# MLX.net
KiCad netlist of a schematic drawn in Altium Designer
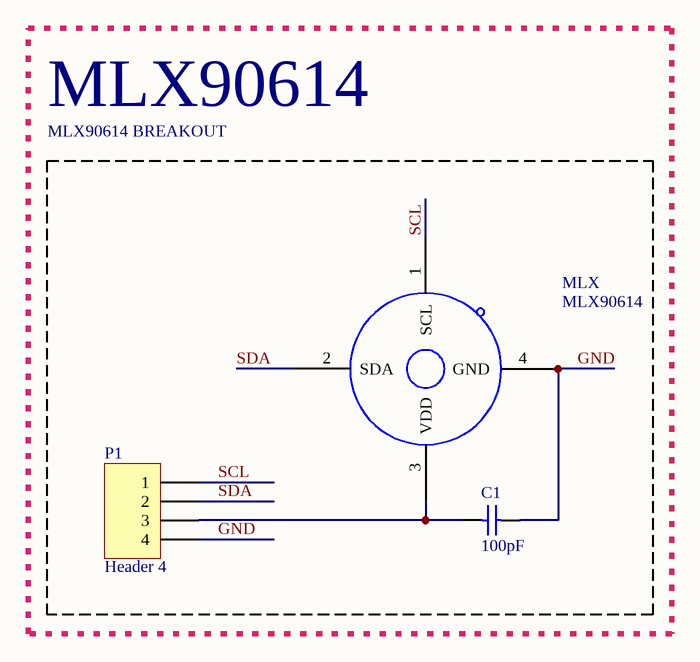
[diagram p0: MLX.SchDoc]

(export (version "E")
  (design (tool "Eeschema 10.0.6"))
  (components
    (comp (ref "C1")
      (value "100pF")
      (footprint "C1206")
      (description "Capacitor (Semiconductor SIM Model)")
      (fields (field (name "Comment") "Cap Semi") (field (name "PUBLISHER") "Altium Limited"))
      (libsource (lib "Miscellaneous Devices") (part "Cap Semi"))
    )
    (comp (ref "MLX")
      (value "MLX90614")
      (footprint "MLX90614")
      (libsource (lib "CustomLibrary") (part "MLX90614"))
    )
    (comp (ref "P1")
      (value "Header 4")
      (footprint "HDR1X4")
      (description "Header, 4-Pin")
      (fields (field (name "PUBLISHER") "Altium Limited"))
      (libsource (lib "Miscellaneous Connectors") (part "Header 4"))
    )
  )
  (nets
    (net (code "1") (name "/GND") (class "Default")
      (node (ref "C1") (pin "1") (pinfunction "1_1") (pintype "passive"))
      (node (ref "MLX") (pin "4") (pinfunction "GND_4") (pintype "passive"))
      (node (ref "P1") (pin "4") (pinfunction "4_4") (pintype "passive"))
    )
    (net (code "2") (name "/SCL") (class "Default")
      (node (ref "MLX") (pin "1") (pinfunction "SCL_1") (pintype "passive"))
      (node (ref "P1") (pin "1") (pinfunction "1_1") (pintype "passive"))
    )
    (net (code "3") (name "/SDA") (class "Default")
      (node (ref "MLX") (pin "2") (pinfunction "SDA_2") (pintype "passive"))
      (node (ref "P1") (pin "2") (pinfunction "2_2") (pintype "passive"))
    )
    (net (code "4") (name "Net-(MLX-VDD)") (class "Default")
      (node (ref "C1") (pin "2") (pinfunction "2_2") (pintype "passive"))
      (node (ref "MLX") (pin "3") (pinfunction "VDD_3") (pintype "passive"))
      (node (ref "P1") (pin "3") (pinfunction "3_3") (pintype "passive"))
    )
  )
)
